# CoffeeScale_esp32s2.net
KiCad netlist of a schematic drawn in Altium Designer
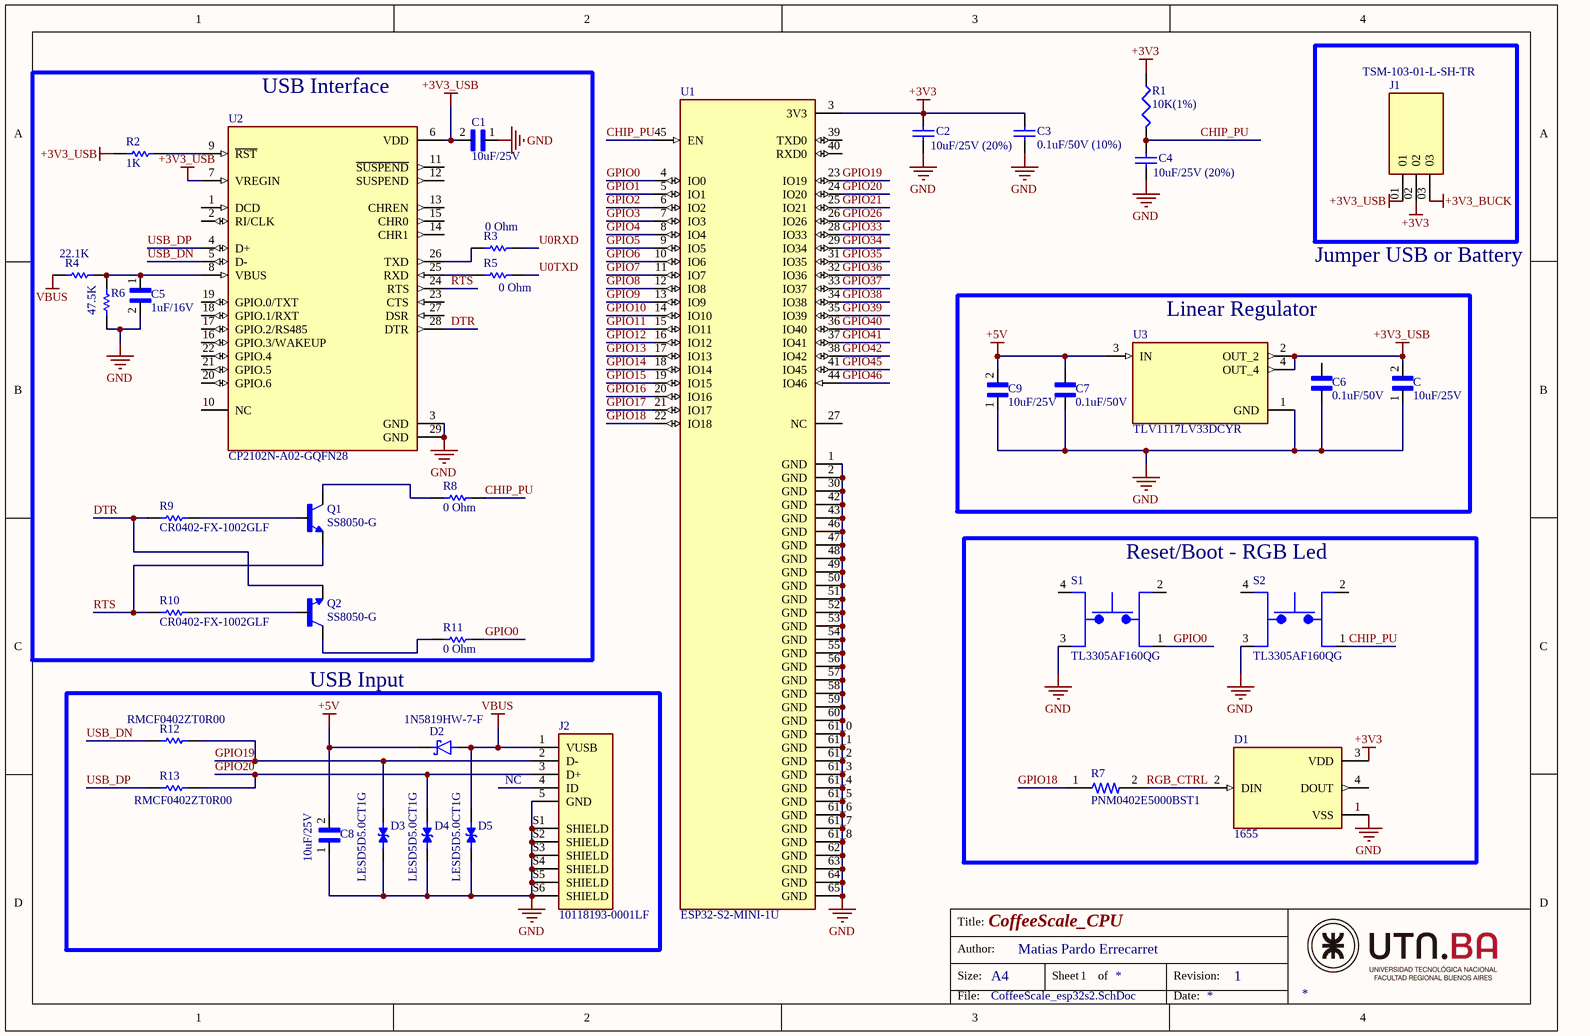
[diagram p0: CoffeeScale_esp32s2.SchDoc]

(export (version "E")
  (design (tool "Eeschema 10.0.6"))
  (components
    (comp (ref "C")
      (value "10uF/25V")
      (footprint "CAPC2012X140N")
      (description "SMD Capacitor X5R_EIA_ with Capacitance: 10uF Tol. 10%. Rated Voltage: 25Vdc")
      (fields (field (name "MP") "GRM21BR61E106KA73K") (field (name "DIGI-KEY_PART_NUMBER") "490-16824-1-ND"))
      (libsource (lib "") (part "GRM21BR61E106KA73K_1"))
    )
    (comp (ref "C1")
      (value "10uF/25V")
      (footprint "CAPC2012X140N")
      (description "SMD Capacitor X5R_EIA_ with Capacitance: 10uF Tol. 10%. Rated Voltage: 25Vdc")
      (fields (field (name "MP") "GRM21BR61E106KA73K") (field (name "DIGI-KEY_PART_NUMBER") "490-16824-1-ND"))
      (libsource (lib "CoffeeScale") (part "GRM21BR61E106KA73K"))
    )
    (comp (ref "C2")
      (value "10uF/25V (20%)")
      (footprint "RAD-0.3")
      (description "Capacitor")
      (fields (field (name "PUBLISHER") "Altium Limited"))
      (libsource (lib "Miscellaneous Devices") (part "Cap"))
    )
    (comp (ref "C3")
      (value "0.1uF/50V (10%)")
      (footprint "RAD-0.3")
      (description "Capacitor")
      (fields (field (name "PUBLISHER") "Altium Limited"))
      (libsource (lib "Miscellaneous Devices") (part "Cap"))
    )
    (comp (ref "C4")
      (value "10uF/25V (20%)")
      (footprint "RAD-0.3")
      (description "Capacitor")
      (fields (field (name "PUBLISHER") "Altium Limited"))
      (libsource (lib "Miscellaneous Devices") (part "Cap"))
    )
    (comp (ref "C5")
      (value "1uF/16V")
      (footprint "CAPC1005X55N")
      (description "1ÂµF Â±10% 16V Ceramic Capacitor X5R 0402 (1005 Metric)")
      (fields (field (name "MP") "CL05A105KO5NNNC") (field (name "MF") "Samsung Electro-Mechanics"))
      (libsource (lib "CoffeeScale") (part "CL05A105KO5NNNC"))
    )
    (comp (ref "C6")
      (value "0.1uF/50V")
      (footprint "CAPC1005X55N")
      (description "SMD capacitor X7R(EIA) with capacitance 0.10uF Tol.10%. Rated voltage 50Vdc 125C")
      (fields (field (name "MF") "Murata Electronics") (field (name "MP") "GRM155R71H104KE14D"))
      (libsource (lib "CoffeeScale") (part "GRM155R71H104KE14D"))
    )
    (comp (ref "C7")
      (value "0.1uF/50V")
      (footprint "CAPC1005X55N")
      (description "SMD capacitor X7R(EIA) with capacitance 0.10uF Tol.10%. Rated voltage 50Vdc 125C")
      (fields (field (name "MF") "Murata Electronics") (field (name "MP") "GRM155R71H104KE14D"))
      (libsource (lib "CoffeeScale") (part "GRM155R71H104KE14D"))
    )
    (comp (ref "C8")
      (value "10uF/25V")
      (footprint "CAPC2012X140N")
      (description "SMD Capacitor X5R_EIA_ with Capacitance: 10uF Tol. 10%. Rated Voltage: 25Vdc")
      (fields (field (name "MP") "GRM21BR61E106KA73K") (field (name "DIGI-KEY_PART_NUMBER") "490-16824-1-ND"))
      (libsource (lib "") (part "GRM21BR61E106KA73K_1"))
    )
    (comp (ref "C9")
      (value "10uF/25V")
      (footprint "CAPC2012X140N")
      (description "SMD Capacitor X5R_EIA_ with Capacitance: 10uF Tol. 10%. Rated Voltage: 25Vdc")
      (fields (field (name "MP") "GRM21BR61E106KA73K") (field (name "DIGI-KEY_PART_NUMBER") "490-16824-1-ND"))
      (libsource (lib "") (part "GRM21BR61E106KA73K_1"))
    )
    (comp (ref "D1")
      (value "1655")
      (footprint "LED_1655")
      (description "Ws2812b 5050 Rgb Led With Integrated Driver Chip Pack Of 10")
      (libsource (lib "CoffeeScale") (part "1655"))
    )
    (comp (ref "D2")
      (value "1N5819HW-7-F")
      (footprint "SOD3715X145N")
      (description "Diode Schottky 40 V 1A Surface Mount SOD-123")
      (fields (field (name "MF") "Diodes Inc."))
      (libsource (lib "CoffeeScale") (part "1N5819HW-7-F"))
    )
    (comp (ref "D3")
      (value "LESD5D5.0CT1G")
      (footprint "TVS_LESD5D5.0CT1G")
      (description "Transient Voltage Suppressors for ESD Protection")
      (fields (field (name "MF") "Leshan Radio Co."))
      (libsource (lib "CoffeeScale") (part "LESD5D5.0CT1G"))
    )
    (comp (ref "D4")
      (value "LESD5D5.0CT1G")
      (footprint "TVS_LESD5D5.0CT1G")
      (description "Transient Voltage Suppressors for ESD Protection")
      (fields (field (name "MF") "Leshan Radio Co."))
      (libsource (lib "CoffeeScale") (part "LESD5D5.0CT1G"))
    )
    (comp (ref "D5")
      (value "LESD5D5.0CT1G")
      (footprint "TVS_LESD5D5.0CT1G")
      (description "Transient Voltage Suppressors for ESD Protection")
      (fields (field (name "MF") "Leshan Radio Co."))
      (libsource (lib "CoffeeScale") (part "LESD5D5.0CT1G"))
    )
    (comp (ref "J1")
      (value "TSM-103-01-L-SH-TR")
      (footprint "SAMTEC_TSM-103-01-L-SH-TR")
      (description "Connector Header Surface Mount, Right Angle 3 position 0.100 (2.54mm)")
      (fields (field (name "MF") "Samtec Inc."))
      (libsource (lib "CoffeeScale") (part "TSM-103-01-L-SH-TR"))
    )
    (comp (ref "J2")
      (value "10118193-0001LF")
      (footprint "AMPHENOL_10118193-0001LF")
      (description "Micro USB 2.0, Input Output Connectors, B TYPE RECEPTACLE")
      (fields (field (name "MF") "Amphenol ICC"))
      (libsource (lib "CoffeeScale") (part "10118193-0001LF"))
    )
    (comp (ref "Q1")
      (value "SS8050-G")
      (footprint "TRANS_SS8050-G")
      (description "Bipolar (BJT) Transistor NPN 25 V 1.5 A 100MHz 300 mW Surface Mount SOT-23-3")
      (fields (field (name "DIGI-KEY_PART_NUMBER") "641-1790-2-ND") (field (name "MP") "SS8050G"))
      (libsource (lib "") (part "SS8050-G_1"))
    )
    (comp (ref "Q2")
      (value "SS8050-G")
      (footprint "TRANS_SS8050-G")
      (description "Bipolar (BJT) Transistor NPN 25 V 1.5 A 100MHz 300 mW Surface Mount SOT-23-3")
      (fields (field (name "DIGI-KEY_PART_NUMBER") "641-1790-2-ND") (field (name "MP") "SS8050G"))
      (libsource (lib "CoffeeScale") (part "SS8050-G"))
    )
    (comp (ref "R1")
      (value "10K(1%)")
      (footprint "J1-0603")
      (description "Resistor")
      (fields (field (name "PUBLISHER") "Altium Limited"))
      (libsource (lib "Miscellaneous Devices") (part "Res3"))
    )
    (comp (ref "R2")
      (value "1K")
      (footprint "RESC1005X40N")
      (description "1 kOhms Â±1% 0.063W, 1/16W Chip Resistor 0402 (1005 Metric) Moisture Resistant Thick Film")
      (fields (field (name "MF") "Yageo") (field (name "MP") "RC0402FR-071KL"))
      (libsource (lib "CoffeeScale") (part "RC0402FR-071KL"))
    )
    (comp (ref "R3")
      (value "0 Ohm")
      (footprint "RESC1005X40")
      (description "0 Ohms Jumper 0.063W, 1/16W Chip Resistor 0402 _1005 Metric_ Automotive AEC-Q200 Thick Film")
      (fields (field (name "MF") "Stackpole Electronics") (field (name "MP") "RMCF0402ZT0R00"))
      (libsource (lib "CoffeeScale") (part "RMCF0402ZT0R00"))
    )
    (comp (ref "R4")
      (value "22.1K")
      (footprint "RESC1005X40N")
      (description "THICK FILM RESISTOR, 22.1KOHM 62.5mW 1%")
      (fields (field (name "MP") "RC0402FR-0722K1L"))
      (libsource (lib "CoffeeScale") (part "RC0402FR-0722K1L"))
    )
    (comp (ref "R5")
      (value "0 Ohm")
      (footprint "RESC1005X40")
      (description "0 Ohms Jumper 0.063W, 1/16W Chip Resistor 0402 _1005 Metric_ Automotive AEC-Q200 Thick Film")
      (fields (field (name "MF") "Stackpole Electronics") (field (name "MP") "RMCF0402ZT0R00"))
      (libsource (lib "CoffeeScale") (part "RMCF0402ZT0R00"))
    )
    (comp (ref "R6")
      (value "47.5K")
      (footprint "RESC1005X40N")
      (description "Res Thick Film 0402 47.5K Ohm 1% 0.063W(1/16W) ??100ppm/??C Epoxy SMD T/R")
      (fields (field (name "MP") "RC0402FR-0747K5L"))
      (libsource (lib "CoffeeScale") (part "RC0402FR-0747K5L"))
    )
    (comp (ref "R7")
      (value "PNM0402E5000BST1")
      (footprint "RESC1005X40")
      (description "500 OHM .1% 25PPM")
      (libsource (lib "CoffeeScale") (part "PNM0402E5000BST1"))
    )
    (comp (ref "R8")
      (value "0 Ohm")
      (footprint "RESC1005X40")
      (description "0 Ohms Jumper 0.063W, 1/16W Chip Resistor 0402 _1005 Metric_ Automotive AEC-Q200 Thick Film")
      (fields (field (name "MF") "Stackpole Electronics") (field (name "MP") "RMCF0402ZT0R00"))
      (libsource (lib "CoffeeScale") (part "RMCF0402ZT0R00"))
    )
    (comp (ref "R9")
      (value "CR0402-FX-1002GLF")
      (footprint "RESC1005X40N")
      (description "Res Thick Film 0402 10K Ohm 1% 1/16W Â±100ppm/Â°C Molded SMD SMD Paper Tape on Plastic Reel")
      (libsource (lib "CoffeeScale") (part "CR0402-FX-1002GLF"))
    )
    (comp (ref "R10")
      (value "CR0402-FX-1002GLF")
      (footprint "RESC1005X40N")
      (description "Res Thick Film 0402 10K Ohm 1% 1/16W Â±100ppm/Â°C Molded SMD SMD Paper Tape on Plastic Reel")
      (libsource (lib "CoffeeScale") (part "CR0402-FX-1002GLF"))
    )
    (comp (ref "R11")
      (value "0 Ohm")
      (footprint "RESC1005X40")
      (description "0 Ohms Jumper 0.063W, 1/16W Chip Resistor 0402 _1005 Metric_ Automotive AEC-Q200 Thick Film")
      (fields (field (name "MF") "Stackpole Electronics") (field (name "MP") "RMCF0402ZT0R00"))
      (libsource (lib "CoffeeScale") (part "RMCF0402ZT0R00"))
    )
    (comp (ref "R12")
      (value "RMCF0402ZT0R00")
      (footprint "RESC1005X40")
      (description "0 Ohms Jumper 0.063W, 1/16W Chip Resistor 0402 _1005 Metric_ Automotive AEC-Q200 Thick Film")
      (fields (field (name "MF") "Stackpole Electronics"))
      (libsource (lib "CoffeeScale") (part "RMCF0402ZT0R00"))
    )
    (comp (ref "R13")
      (value "RMCF0402ZT0R00")
      (footprint "RESC1005X40")
      (description "0 Ohms Jumper 0.063W, 1/16W Chip Resistor 0402 _1005 Metric_ Automotive AEC-Q200 Thick Film")
      (fields (field (name "MF") "Stackpole Electronics"))
      (libsource (lib "CoffeeScale") (part "RMCF0402ZT0R00"))
    )
    (comp (ref "S1")
      (value "TL3305AF160QG")
      (footprint "SW_TL3305AF160QG")
      (description "Tactile Switch SPST-NO Top Actuated Surface Mount")
      (fields (field (name "MF") "E-Switch"))
      (libsource (lib "CoffeeScale") (part "TL3305AF160QG"))
    )
    (comp (ref "S2")
      (value "TL3305AF160QG")
      (footprint "SW_TL3305AF160QG")
      (description "Tactile Switch SPST-NO Top Actuated Surface Mount")
      (fields (field (name "MF") "E-Switch"))
      (libsource (lib "CoffeeScale") (part "TL3305AF160QG"))
    )
    (comp (ref "U1")
      (value "ESP32-S2-MINI-1U")
      (footprint "XCVR_ESP32-S2-MINI-1U:XCVR_ESP32-S2-MINI-1U")
      (description "WiFi 802.11b/g/n Transceiver Module 2.412GHz ~ 2.484GHz Antenna Not Included Surface Mount")
      (fields (field (name "MF") "Espressif Systems"))
      (libsource (lib "CoffeeScale") (part "ESP32-S2-MINI-1U"))
    )
    (comp (ref "U2")
      (value "CP2102N-A02-GQFN28")
      (footprint "QFN50P500X500X80-29N")
      (description "USB Bridge, USB to UART USB 2.0 UART Interface 28-QFN (5x5)")
      (fields (field (name "MF") "Silicon Labs"))
      (libsource (lib "CoffeeScale") (part "CP2102N-A02-GQFN28"))
    )
    (comp (ref "U3")
      (value "TLV1117LV33DCYR")
      (footprint "VREG_TLV1117LV33DCYR")
      (description "1-A, low-dropout voltage regulator")
      (fields (field (name "DIGI-KEY_PART_NUMBER") "296-28778-2-ND") (field (name "MF") "Texas Instruments"))
      (libsource (lib "CoffeeScale") (part "TLV1117LV33DCYR"))
    )
  )
  (nets
    (net (code "1") (name "+3V3") (class "Default")
      (node (ref "C2") (pin "2") (pinfunction "2_2") (pintype "passive"))
      (node (ref "C3") (pin "2") (pinfunction "2_2") (pintype "passive"))
      (node (ref "D1") (pin "3") (pinfunction "VDD_3") (pintype "power_in"))
      (node (ref "J1") (pin "02") (pinfunction "02_02") (pintype "passive"))
      (node (ref "R1") (pin "1") (pinfunction "1_1") (pintype "passive"))
      (node (ref "U1") (pin "3") (pinfunction "3V3_3") (pintype "power_in"))
    )
    (net (code "2") (name "+3V3_BUCK") (class "Default")
      (node (ref "J1") (pin "03") (pinfunction "03_03") (pintype "passive"))
    )
    (net (code "3") (name "+3V3_USB") (class "Default")
      (node (ref "C") (pin "2") (pinfunction "2_2") (pintype "passive"))
      (node (ref "C1") (pin "2") (pinfunction "2_2") (pintype "passive"))
      (node (ref "J1") (pin "01") (pinfunction "01_01") (pintype "passive"))
      (node (ref "R2") (pin "1") (pinfunction "1_1") (pintype "passive"))
      (node (ref "U2") (pin "6") (pinfunction "VDD_6") (pintype "power_in"))
      (node (ref "U2") (pin "7") (pinfunction "VREGIN_7") (pintype "input"))
      (node (ref "U3") (pin "2") (pinfunction "OUT_2_2") (pintype "output"))
      (node (ref "U3") (pin "4") (pinfunction "OUT_4_4") (pintype "output"))
    )
    (net (code "4") (name "+5V") (class "Default")
      (node (ref "C7") (pin "2") (pinfunction "2_2") (pintype "passive"))
      (node (ref "C8") (pin "2") (pinfunction "2_2") (pintype "passive"))
      (node (ref "C9") (pin "2") (pinfunction "2_2") (pintype "passive"))
      (node (ref "D2") (pin "C") (pinfunction "K_C") (pintype "passive"))
      (node (ref "U3") (pin "3") (pinfunction "IN_3") (pintype "input"))
    )
    (net (code "5") (name "/CHIP_PU") (class "Default")
      (node (ref "C4") (pin "2") (pinfunction "2_2") (pintype "passive"))
      (node (ref "R1") (pin "2") (pinfunction "2_2") (pintype "passive"))
      (node (ref "R8") (pin "2") (pinfunction "2_2") (pintype "passive"))
      (node (ref "S2") (pin "1") (pinfunction "1_1") (pintype "passive"))
      (node (ref "U1") (pin "45") (pinfunction "EN_45") (pintype "input"))
    )
    (net (code "6") (name "/DTR") (class "Default")
      (node (ref "Q2") (pin "2") (pinfunction "E_2") (pintype "passive"))
      (node (ref "R9") (pin "1") (pinfunction "1_1") (pintype "passive"))
      (node (ref "U2") (pin "28") (pinfunction "DTR_28") (pintype "output"))
    )
    (net (code "7") (name "/GPIO0") (class "Default")
      (node (ref "R11") (pin "2") (pinfunction "2_2") (pintype "passive"))
      (node (ref "S1") (pin "1") (pinfunction "1_1") (pintype "passive"))
      (node (ref "U1") (pin "4") (pinfunction "IO0_4") (pintype "bidirectional"))
    )
    (net (code "8") (name "/GPIO1") (class "Default")
      (node (ref "U1") (pin "5") (pinfunction "IO1_5") (pintype "bidirectional"))
    )
    (net (code "9") (name "/GPIO2") (class "Default")
      (node (ref "U1") (pin "6") (pinfunction "IO2_6") (pintype "bidirectional"))
    )
    (net (code "10") (name "/GPIO3") (class "Default")
      (node (ref "U1") (pin "7") (pinfunction "IO3_7") (pintype "bidirectional"))
    )
    (net (code "11") (name "/GPIO4") (class "Default")
      (node (ref "U1") (pin "8") (pinfunction "IO4_8") (pintype "bidirectional"))
    )
    (net (code "12") (name "/GPIO5") (class "Default")
      (node (ref "U1") (pin "9") (pinfunction "IO5_9") (pintype "bidirectional"))
    )
    (net (code "13") (name "/GPIO6") (class "Default")
      (node (ref "U1") (pin "10") (pinfunction "IO6_10") (pintype "bidirectional"))
    )
    (net (code "14") (name "/GPIO7") (class "Default")
      (node (ref "U1") (pin "11") (pinfunction "IO7_11") (pintype "bidirectional"))
    )
    (net (code "15") (name "/GPIO8") (class "Default")
      (node (ref "U1") (pin "12") (pinfunction "IO8_12") (pintype "bidirectional"))
    )
    (net (code "16") (name "/GPIO9") (class "Default")
      (node (ref "U1") (pin "13") (pinfunction "IO9_13") (pintype "bidirectional"))
    )
    (net (code "17") (name "/GPIO10") (class "Default")
      (node (ref "U1") (pin "14") (pinfunction "IO10_14") (pintype "bidirectional"))
    )
    (net (code "18") (name "/GPIO11") (class "Default")
      (node (ref "U1") (pin "15") (pinfunction "IO11_15") (pintype "bidirectional"))
    )
    (net (code "19") (name "/GPIO12") (class "Default")
      (node (ref "U1") (pin "16") (pinfunction "IO12_16") (pintype "bidirectional"))
    )
    (net (code "20") (name "/GPIO13") (class "Default")
      (node (ref "U1") (pin "17") (pinfunction "IO13_17") (pintype "bidirectional"))
    )
    (net (code "21") (name "/GPIO14") (class "Default")
      (node (ref "U1") (pin "18") (pinfunction "IO14_18") (pintype "bidirectional"))
    )
    (net (code "22") (name "/GPIO15") (class "Default")
      (node (ref "U1") (pin "19") (pinfunction "IO15_19") (pintype "bidirectional"))
    )
    (net (code "23") (name "/GPIO16") (class "Default")
      (node (ref "U1") (pin "20") (pinfunction "IO16_20") (pintype "bidirectional"))
    )
    (net (code "24") (name "/GPIO17") (class "Default")
      (node (ref "U1") (pin "21") (pinfunction "IO17_21") (pintype "bidirectional"))
    )
    (net (code "25") (name "/GPIO18") (class "Default")
      (node (ref "R7") (pin "1") (pinfunction "1_1") (pintype "passive"))
      (node (ref "U1") (pin "22") (pinfunction "IO18_22") (pintype "bidirectional"))
    )
    (net (code "26") (name "/GPIO19") (class "Default")
      (node (ref "D3") (pin "2") (pinfunction "2_2") (pintype "passive"))
      (node (ref "J2") (pin "2") (pinfunction "D-_2") (pintype "passive"))
      (node (ref "R12") (pin "2") (pinfunction "2_2") (pintype "passive"))
      (node (ref "U1") (pin "23") (pinfunction "IO19_23") (pintype "bidirectional"))
    )
    (net (code "27") (name "/GPIO20") (class "Default")
      (node (ref "D4") (pin "2") (pinfunction "2_2") (pintype "passive"))
      (node (ref "J2") (pin "3") (pinfunction "D+_3") (pintype "passive"))
      (node (ref "R13") (pin "2") (pinfunction "2_2") (pintype "passive"))
      (node (ref "U1") (pin "24") (pinfunction "IO20_24") (pintype "bidirectional"))
    )
    (net (code "28") (name "/GPIO21") (class "Default")
      (node (ref "U1") (pin "25") (pinfunction "IO21_25") (pintype "bidirectional"))
    )
    (net (code "29") (name "/GPIO26") (class "Default")
      (node (ref "U1") (pin "26") (pinfunction "IO26_26") (pintype "bidirectional"))
    )
    (net (code "30") (name "/GPIO33") (class "Default")
      (node (ref "U1") (pin "28") (pinfunction "IO33_28") (pintype "bidirectional"))
    )
    (net (code "31") (name "/GPIO34") (class "Default")
      (node (ref "U1") (pin "29") (pinfunction "IO34_29") (pintype "bidirectional"))
    )
    (net (code "32") (name "/GPIO35") (class "Default")
      (node (ref "U1") (pin "31") (pinfunction "IO35_31") (pintype "bidirectional"))
    )
    (net (code "33") (name "/GPIO36") (class "Default")
      (node (ref "U1") (pin "32") (pinfunction "IO36_32") (pintype "bidirectional"))
    )
    (net (code "34") (name "/GPIO37") (class "Default")
      (node (ref "U1") (pin "33") (pinfunction "IO37_33") (pintype "bidirectional"))
    )
    (net (code "35") (name "/GPIO38") (class "Default")
      (node (ref "U1") (pin "34") (pinfunction "IO38_34") (pintype "bidirectional"))
    )
    (net (code "36") (name "/GPIO39") (class "Default")
      (node (ref "U1") (pin "35") (pinfunction "IO39_35") (pintype "bidirectional"))
    )
    (net (code "37") (name "/GPIO40") (class "Default")
      (node (ref "U1") (pin "36") (pinfunction "IO40_36") (pintype "bidirectional"))
    )
    (net (code "38") (name "/GPIO41") (class "Default")
      (node (ref "U1") (pin "37") (pinfunction "IO41_37") (pintype "bidirectional"))
    )
    (net (code "39") (name "/GPIO42") (class "Default")
      (node (ref "U1") (pin "38") (pinfunction "IO42_38") (pintype "bidirectional"))
    )
    (net (code "40") (name "/GPIO45") (class "Default")
      (node (ref "U1") (pin "41") (pinfunction "IO45_41") (pintype "bidirectional"))
    )
    (net (code "41") (name "/GPIO46") (class "Default")
      (node (ref "U1") (pin "44") (pinfunction "IO46_44") (pintype "input"))
    )
    (net (code "42") (name "/RGB_CTRL") (class "Default")
      (node (ref "D1") (pin "2") (pinfunction "DIN_2") (pintype "input"))
      (node (ref "R7") (pin "2") (pinfunction "2_2") (pintype "passive"))
    )
    (net (code "43") (name "/RTS") (class "Default")
      (node (ref "Q1") (pin "2") (pinfunction "E_2") (pintype "passive"))
      (node (ref "R10") (pin "1") (pinfunction "1_1") (pintype "passive"))
      (node (ref "U2") (pin "24") (pinfunction "RTS_24") (pintype "output"))
    )
    (net (code "44") (name "/U0RXD") (class "Default")
      (node (ref "R3") (pin "2") (pinfunction "2_2") (pintype "passive"))
    )
    (net (code "45") (name "/U0TXD") (class "Default")
      (node (ref "R5") (pin "2") (pinfunction "2_2") (pintype "passive"))
    )
    (net (code "46") (name "/USB_DN") (class "Default")
      (node (ref "R12") (pin "1") (pinfunction "1_1") (pintype "passive"))
      (node (ref "U2") (pin "5") (pinfunction "D-_5") (pintype "bidirectional"))
    )
    (net (code "47") (name "/USB_DP") (class "Default")
      (node (ref "R13") (pin "1") (pinfunction "1_1") (pintype "passive"))
      (node (ref "U2") (pin "4") (pinfunction "D+_4") (pintype "bidirectional"))
    )
    (net (code "48") (name "GND") (class "Default")
      (node (ref "C") (pin "1") (pinfunction "1_1") (pintype "passive"))
      (node (ref "C1") (pin "1") (pinfunction "1_1") (pintype "passive"))
      (node (ref "C2") (pin "1") (pinfunction "1_1") (pintype "passive"))
      (node (ref "C3") (pin "1") (pinfunction "1_1") (pintype "passive"))
      (node (ref "C4") (pin "1") (pinfunction "1_1") (pintype "passive"))
      (node (ref "C5") (pin "2") (pinfunction "2_2") (pintype "passive"))
      (node (ref "C6") (pin "1") (pinfunction "1_1") (pintype "passive"))
      (node (ref "C7") (pin "1") (pinfunction "1_1") (pintype "passive"))
      (node (ref "C8") (pin "1") (pinfunction "1_1") (pintype "passive"))
      (node (ref "C9") (pin "1") (pinfunction "1_1") (pintype "passive"))
      (node (ref "D1") (pin "1") (pinfunction "VSS_1") (pintype "power_in"))
      (node (ref "D3") (pin "1") (pinfunction "1_1") (pintype "passive"))
      (node (ref "D4") (pin "1") (pinfunction "1_1") (pintype "passive"))
      (node (ref "D5") (pin "1") (pinfunction "1_1") (pintype "passive"))
      (node (ref "J2") (pin "5") (pinfunction "GND_5") (pintype "passive"))
      (node (ref "J2") (pin "S1") (pinfunction "SHIELD_S1") (pintype "passive"))
      (node (ref "J2") (pin "S2") (pinfunction "SHIELD_S2") (pintype "passive"))
      (node (ref "J2") (pin "S3") (pinfunction "SHIELD_S3") (pintype "passive"))
      (node (ref "J2") (pin "S4") (pinfunction "SHIELD_S4") (pintype "passive"))
      (node (ref "J2") (pin "S5") (pinfunction "SHIELD_S5") (pintype "passive"))
      (node (ref "J2") (pin "S6") (pinfunction "SHIELD_S6") (pintype "passive"))
      (node (ref "R6") (pin "1") (pinfunction "1_1") (pintype "passive"))
      (node (ref "S1") (pin "3") (pinfunction "3_3") (pintype "passive"))
      (node (ref "S2") (pin "3") (pinfunction "3_3") (pintype "passive"))
      (node (ref "U1") (pin "1") (pinfunction "GND_1") (pintype "power_in"))
      (node (ref "U1") (pin "2") (pinfunction "GND_2") (pintype "power_in"))
      (node (ref "U1") (pin "30") (pinfunction "GND_30") (pintype "power_in"))
      (node (ref "U1") (pin "42") (pinfunction "GND_42") (pintype "power_in"))
      (node (ref "U1") (pin "43") (pinfunction "GND_43") (pintype "power_in"))
      (node (ref "U1") (pin "46") (pinfunction "GND_46") (pintype "power_in"))
      (node (ref "U1") (pin "47") (pinfunction "GND_47") (pintype "power_in"))
      (node (ref "U1") (pin "48") (pinfunction "GND_48") (pintype "power_in"))
      (node (ref "U1") (pin "49") (pinfunction "GND_49") (pintype "power_in"))
      (node (ref "U1") (pin "50") (pinfunction "GND_50") (pintype "power_in"))
      (node (ref "U1") (pin "51") (pinfunction "GND_51") (pintype "power_in"))
      (node (ref "U1") (pin "52") (pinfunction "GND_52") (pintype "power_in"))
      (node (ref "U1") (pin "53") (pinfunction "GND_53") (pintype "power_in"))
      (node (ref "U1") (pin "54") (pinfunction "GND_54") (pintype "power_in"))
      (node (ref "U1") (pin "55") (pinfunction "GND_55") (pintype "power_in"))
      (node (ref "U1") (pin "56") (pinfunction "GND_56") (pintype "power_in"))
      (node (ref "U1") (pin "57") (pinfunction "GND_57") (pintype "power_in"))
      (node (ref "U1") (pin "58") (pinfunction "GND_58") (pintype "power_in"))
      (node (ref "U1") (pin "59") (pinfunction "GND_59") (pintype "power_in"))
      (node (ref "U1") (pin "60") (pinfunction "GND_60") (pintype "power_in"))
      (node (ref "U1") (pin "61_0") (pinfunction "GND_61_0") (pintype "power_in"))
      (node (ref "U1") (pin "61_1") (pinfunction "GND_61_1") (pintype "power_in"))
      (node (ref "U1") (pin "61_2") (pinfunction "GND_61_2") (pintype "power_in"))
      (node (ref "U1") (pin "61_3") (pinfunction "GND_61_3") (pintype "power_in"))
      (node (ref "U1") (pin "61_4") (pinfunction "GND_61_4") (pintype "power_in"))
      (node (ref "U1") (pin "61_5") (pinfunction "GND_61_5") (pintype "power_in"))
      (node (ref "U1") (pin "61_6") (pinfunction "GND_61_6") (pintype "power_in"))
      (node (ref "U1") (pin "61_7") (pinfunction "GND_61_7") (pintype "power_in"))
      (node (ref "U1") (pin "61_8") (pinfunction "GND_61_8") (pintype "power_in"))
      (node (ref "U1") (pin "62") (pinfunction "GND_62") (pintype "power_in"))
      (node (ref "U1") (pin "63") (pinfunction "GND_63") (pintype "power_in"))
      (node (ref "U1") (pin "64") (pinfunction "GND_64") (pintype "power_in"))
      (node (ref "U1") (pin "65") (pinfunction "GND_65") (pintype "power_in"))
      (node (ref "U2") (pin "29") (pinfunction "GND_29") (pintype "power_in"))
      (node (ref "U2") (pin "3") (pinfunction "GND_3") (pintype "power_in"))
      (node (ref "U3") (pin "1") (pinfunction "GND_1") (pintype "power_in"))
    )
    (net (code "49") (name "Net-(Q1-B)") (class "Default")
      (node (ref "Q1") (pin "1") (pinfunction "B_1") (pintype "passive"))
      (node (ref "R9") (pin "2") (pinfunction "2_2") (pintype "passive"))
    )
    (net (code "50") (name "Net-(Q1-C)") (class "Default")
      (node (ref "Q1") (pin "3") (pinfunction "C_3") (pintype "passive"))
      (node (ref "R8") (pin "1") (pinfunction "1_1") (pintype "passive"))
    )
    (net (code "51") (name "Net-(Q2-B)") (class "Default")
      (node (ref "Q2") (pin "1") (pinfunction "B_1") (pintype "passive"))
      (node (ref "R10") (pin "2") (pinfunction "2_2") (pintype "passive"))
    )
    (net (code "52") (name "Net-(Q2-C)") (class "Default")
      (node (ref "Q2") (pin "3") (pinfunction "C_3") (pintype "passive"))
      (node (ref "R11") (pin "1") (pinfunction "1_1") (pintype "passive"))
    )
    (net (code "53") (name "Net-(U2-RXD)") (class "Default")
      (node (ref "R5") (pin "1") (pinfunction "1_1") (pintype "passive"))
      (node (ref "U2") (pin "25") (pinfunction "RXD_25") (pintype "input"))
    )
    (net (code "54") (name "Net-(U2-TXD)") (class "Default")
      (node (ref "R3") (pin "1") (pinfunction "1_1") (pintype "passive"))
      (node (ref "U2") (pin "26") (pinfunction "TXD_26") (pintype "output"))
    )
    (net (code "55") (name "Net-(U2-VBUS)") (class "Default")
      (node (ref "C5") (pin "1") (pinfunction "1_1") (pintype "passive"))
      (node (ref "R4") (pin "2") (pinfunction "2_2") (pintype "passive"))
      (node (ref "R6") (pin "2") (pinfunction "2_2") (pintype "passive"))
      (node (ref "U2") (pin "8") (pinfunction "VBUS_8") (pintype "input"))
    )
    (net (code "56") (name "Net-(U2-~{RST})") (class "Default")
      (node (ref "R2") (pin "2") (pinfunction "2_2") (pintype "passive"))
      (node (ref "U2") (pin "9") (pinfunction "~{RST}_9") (pintype "input"))
    )
    (net (code "57") (name "VBUS") (class "Default")
      (node (ref "D2") (pin "A") (pinfunction "A_A") (pintype "passive"))
      (node (ref "D5") (pin "2") (pinfunction "2_2") (pintype "passive"))
      (node (ref "J2") (pin "1") (pinfunction "VUSB_1") (pintype "passive"))
      (node (ref "R4") (pin "1") (pinfunction "1_1") (pintype "passive"))
    )
    (net (code "58") (name "unconnected-(C6-Pad2)") (class "Default")
      (node (ref "C6") (pin "2") (pinfunction "2_2") (pintype "passive"))
    )
    (net (code "59") (name "unconnected-(D1-DOUT-Pad4)") (class "Default")
      (node (ref "D1") (pin "4") (pinfunction "DOUT_4") (pintype "output"))
    )
    (net (code "60") (name "unconnected-(J2-ID-Pad4)") (class "Default")
      (node (ref "J2") (pin "4") (pinfunction "ID_4") (pintype "passive"))
    )
    (net (code "61") (name "unconnected-(S1-Pad2)") (class "Default")
      (node (ref "S1") (pin "2") (pinfunction "2_2") (pintype "passive"))
    )
    (net (code "62") (name "unconnected-(S1-Pad4)") (class "Default")
      (node (ref "S1") (pin "4") (pinfunction "4_4") (pintype "passive"))
    )
    (net (code "63") (name "unconnected-(S2-Pad2)") (class "Default")
      (node (ref "S2") (pin "2") (pinfunction "2_2") (pintype "passive"))
    )
    (net (code "64") (name "unconnected-(S2-Pad4)") (class "Default")
      (node (ref "S2") (pin "4") (pinfunction "4_4") (pintype "passive"))
    )
    (net (code "65") (name "unconnected-(U1-NC-Pad27)") (class "Default")
      (node (ref "U1") (pin "27") (pinfunction "NC_27") (pintype "passive"))
    )
    (net (code "66") (name "unconnected-(U1-RXD0-Pad40)") (class "Default")
      (node (ref "U1") (pin "40") (pinfunction "RXD0_40") (pintype "bidirectional"))
    )
    (net (code "67") (name "unconnected-(U1-TXD0-Pad39)") (class "Default")
      (node (ref "U1") (pin "39") (pinfunction "TXD0_39") (pintype "bidirectional"))
    )
    (net (code "68") (name "unconnected-(U2-CHR0-Pad15)") (class "Default")
      (node (ref "U2") (pin "15") (pinfunction "CHR0_15") (pintype "output"))
    )
    (net (code "69") (name "unconnected-(U2-CHR1-Pad14)") (class "Default")
      (node (ref "U2") (pin "14") (pinfunction "CHR1_14") (pintype "output"))
    )
    (net (code "70") (name "unconnected-(U2-CHREN-Pad13)") (class "Default")
      (node (ref "U2") (pin "13") (pinfunction "CHREN_13") (pintype "output"))
    )
    (net (code "71") (name "unconnected-(U2-CTS-Pad23)") (class "Default")
      (node (ref "U2") (pin "23") (pinfunction "CTS_23") (pintype "input"))
    )
    (net (code "72") (name "unconnected-(U2-DCD-Pad1)") (class "Default")
      (node (ref "U2") (pin "1") (pinfunction "DCD_1") (pintype "input"))
    )
    (net (code "73") (name "unconnected-(U2-DSR-Pad27)") (class "Default")
      (node (ref "U2") (pin "27") (pinfunction "DSR_27") (pintype "input"))
    )
    (net (code "74") (name "unconnected-(U2-GPIO.0{slash}TXT-Pad19)") (class "Default")
      (node (ref "U2") (pin "19") (pinfunction "GPIO.0/TXT_19") (pintype "bidirectional"))
    )
    (net (code "75") (name "unconnected-(U2-GPIO.1{slash}RXT-Pad18)") (class "Default")
      (node (ref "U2") (pin "18") (pinfunction "GPIO.1/RXT_18") (pintype "bidirectional"))
    )
    (net (code "76") (name "unconnected-(U2-GPIO.2{slash}RS485-Pad17)") (class "Default")
      (node (ref "U2") (pin "17") (pinfunction "GPIO.2/RS485_17") (pintype "bidirectional"))
    )
    (net (code "77") (name "unconnected-(U2-GPIO.3{slash}WAKEUP-Pad16)") (class "Default")
      (node (ref "U2") (pin "16") (pinfunction "GPIO.3/WAKEUP_16") (pintype "bidirectional"))
    )
    (net (code "78") (name "unconnected-(U2-GPIO.4-Pad22)") (class "Default")
      (node (ref "U2") (pin "22") (pinfunction "GPIO.4_22") (pintype "bidirectional"))
    )
    (net (code "79") (name "unconnected-(U2-GPIO.5-Pad21)") (class "Default")
      (node (ref "U2") (pin "21") (pinfunction "GPIO.5_21") (pintype "bidirectional"))
    )
    (net (code "80") (name "unconnected-(U2-GPIO.6-Pad20)") (class "Default")
      (node (ref "U2") (pin "20") (pinfunction "GPIO.6_20") (pintype "bidirectional"))
    )
    (net (code "81") (name "unconnected-(U2-NC-Pad10)") (class "Default")
      (node (ref "U2") (pin "10") (pinfunction "NC_10") (pintype "passive"))
    )
    (net (code "82") (name "unconnected-(U2-RI{slash}CLK-Pad2)") (class "Default")
      (node (ref "U2") (pin "2") (pinfunction "RI/CLK_2") (pintype "bidirectional"))
    )
    (net (code "83") (name "unconnected-(U2-SUSPEND-Pad12)") (class "Default")
      (node (ref "U2") (pin "12") (pinfunction "SUSPEND_12") (pintype "output"))
    )
    (net (code "84") (name "unconnected-(U2-~{SUSPEND}-Pad11)") (class "Default")
      (node (ref "U2") (pin "11") (pinfunction "~{SUSPEND}_11") (pintype "output"))
    )
  )
)
